# ivo_A_v1_1.net
KiCad netlist of a schematic drawn in EAGLE
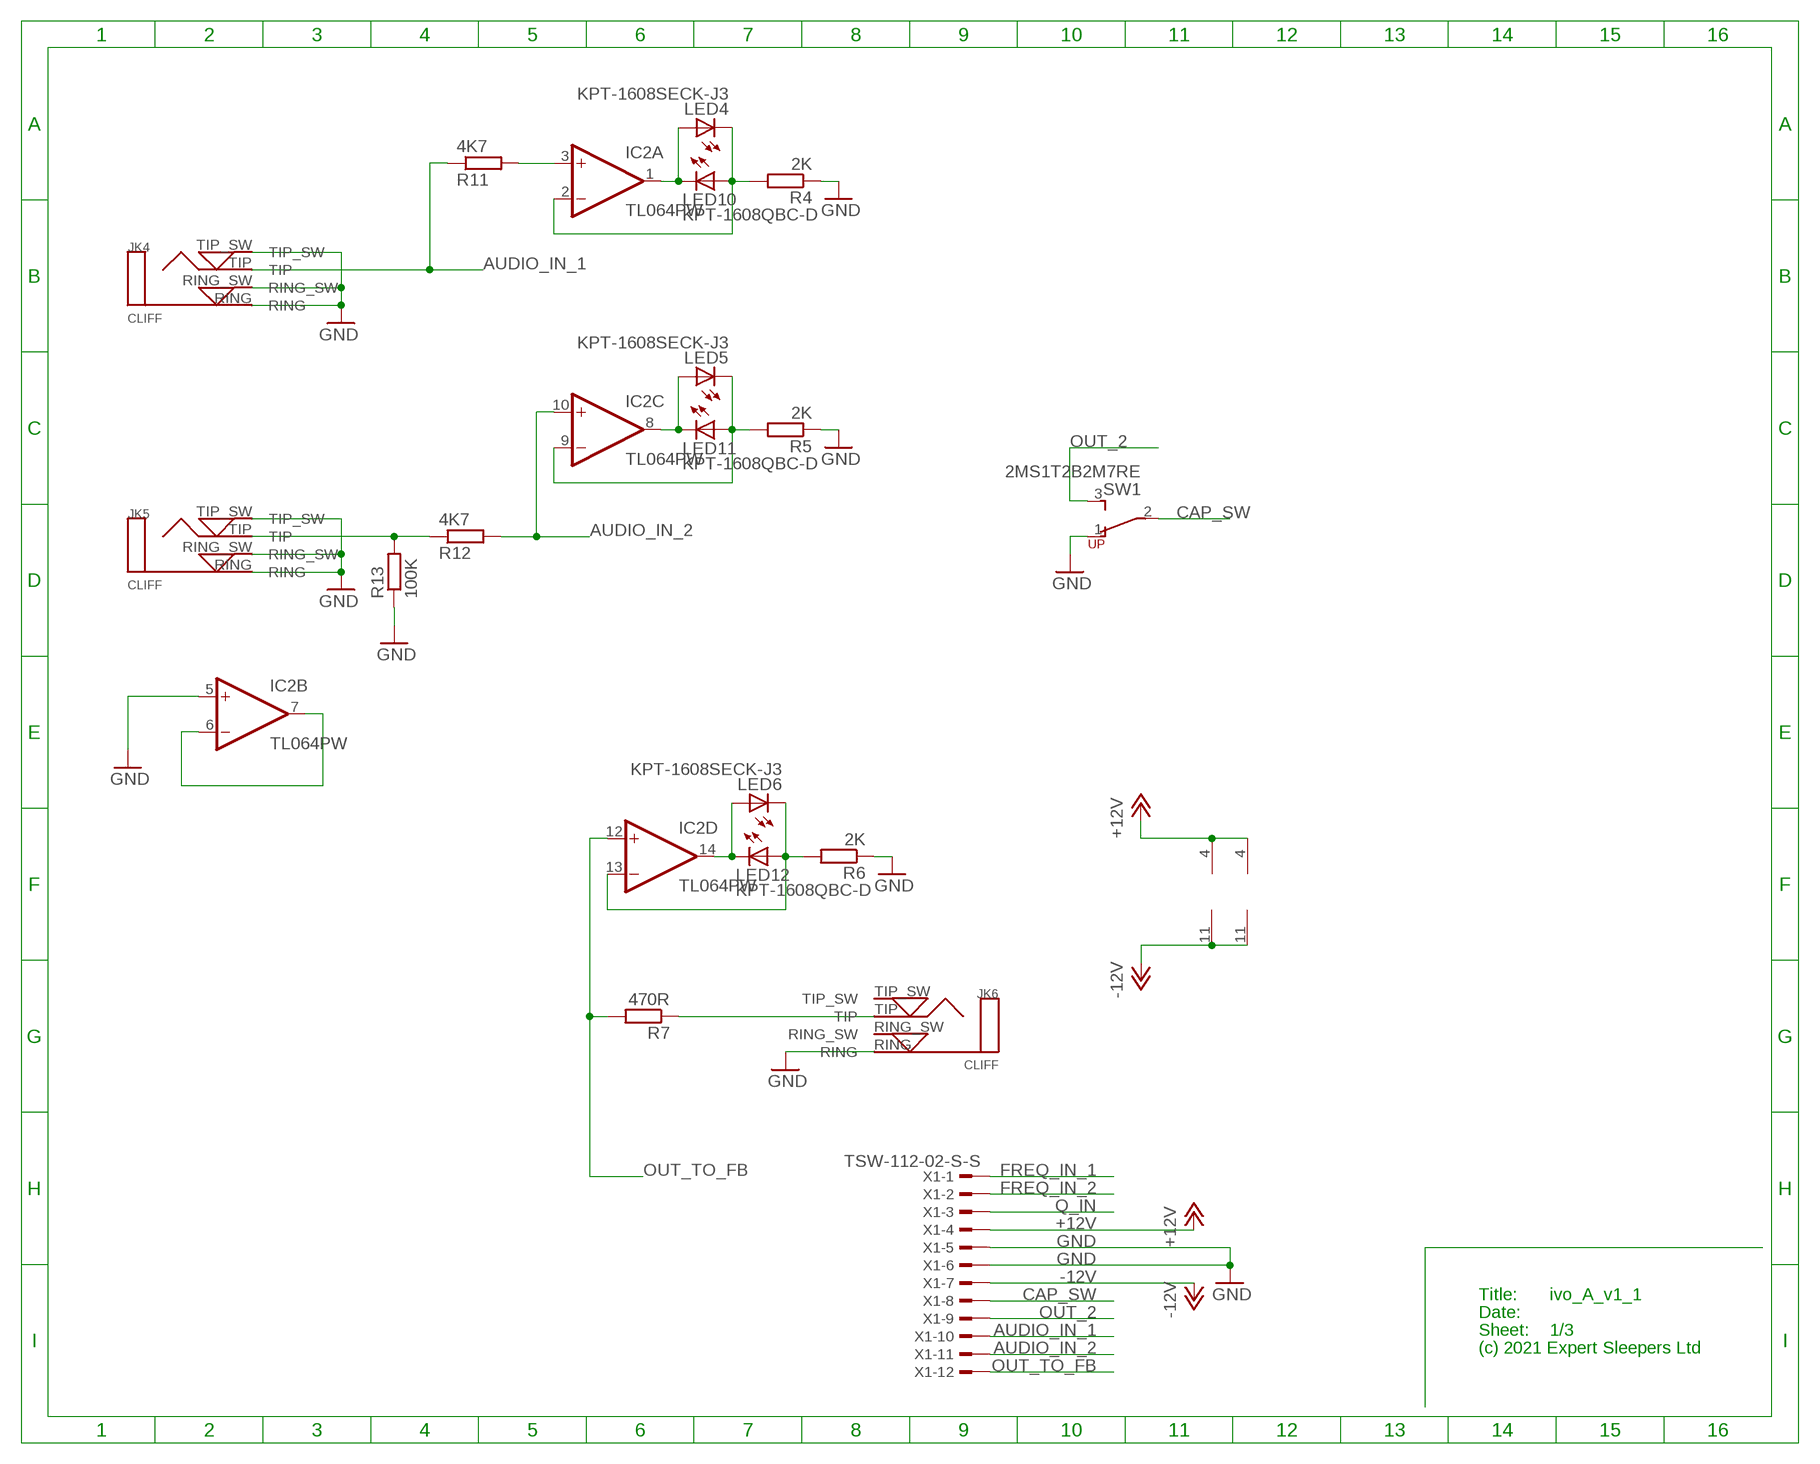
[diagram p0: schematic, sheet 1]
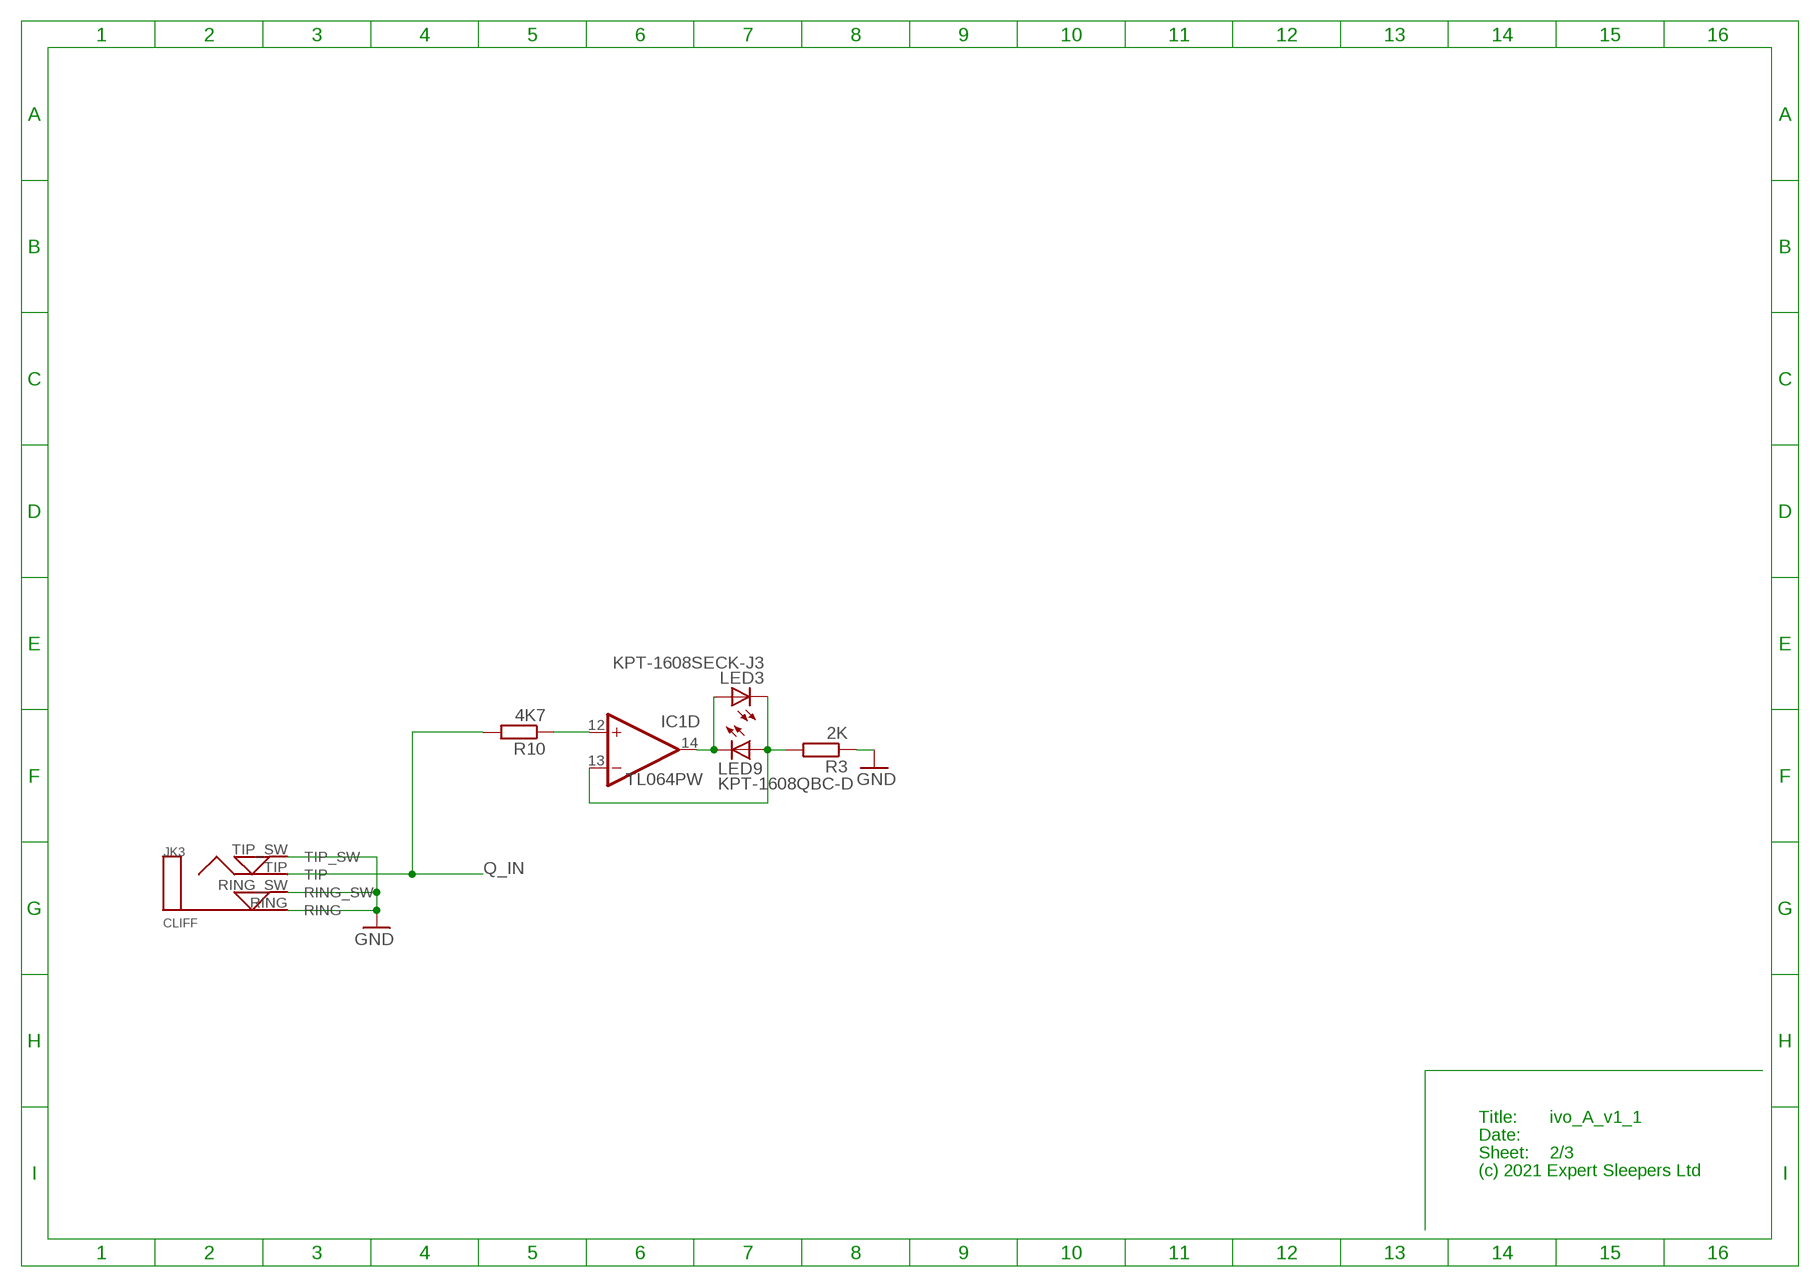
[diagram p1: schematic, sheet 2]
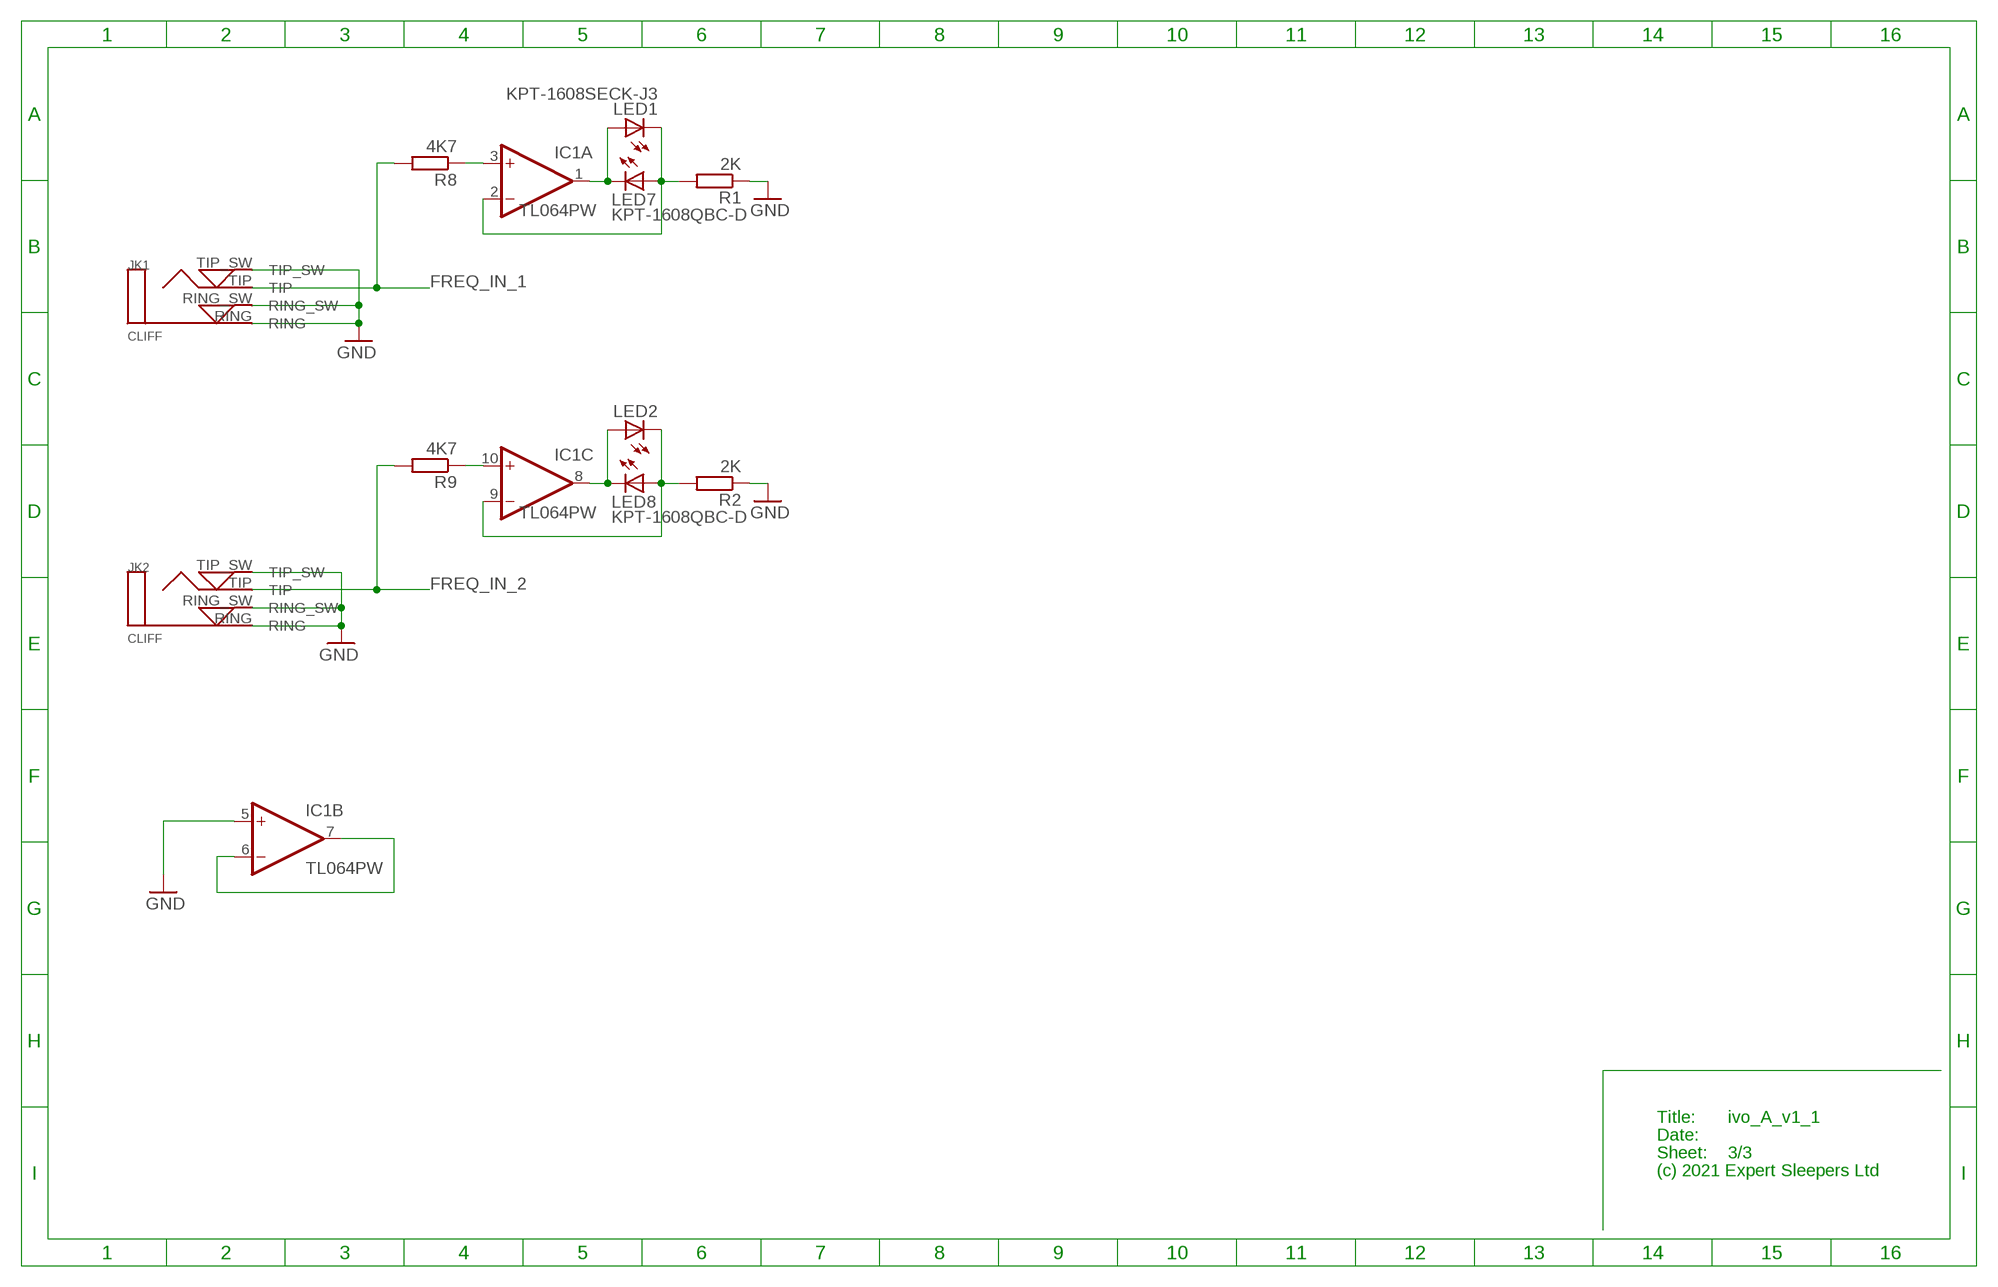
[diagram p2: schematic, sheet 3]

(export (version "E")
  (design (tool "Eeschema 10.0.6"))
  (components
    (comp (ref "IC1")
      (value "TL064PW")
      (footprint "eagle-import:PW_R-PDSO-G14")
      (libsource (lib "eagle-import") (part "TL074PW"))
    )
    (comp (ref "IC2")
      (value "TL064PW")
      (footprint "eagle-import:PW_R-PDSO-G14")
      (libsource (lib "eagle-import") (part "TL074PW"))
    )
    (comp (ref "JK4")
      (value "CLIFF")
      (footprint "eagle-import:CLIFF3.5MMPCB")
      (libsource (lib "eagle-import") (part "CLIFF3.5MM_PCB_SW_JK"))
    )
    (comp (ref "JK5")
      (value "CLIFF")
      (footprint "eagle-import:CLIFF3.5MMPCB")
      (libsource (lib "eagle-import") (part "CLIFF3.5MM_PCB_SW_JK"))
    )
    (comp (ref "JK6")
      (value "CLIFF")
      (footprint "eagle-import:CLIFF3.5MMPCB")
      (libsource (lib "eagle-import") (part "CLIFF3.5MM_PCB_SW_JK"))
    )
    (comp (ref "LED4")
      (value "KPT-1608SECK-J3")
      (footprint "eagle-import:CHIPLED_0603_LEFT")
      (libsource (lib "eagle-import") (part "KPT-1608SECK-J3"))
    )
    (comp (ref "LED5")
      (value "KPT-1608SECK-J3")
      (footprint "eagle-import:CHIPLED_0603_LEFT")
      (libsource (lib "eagle-import") (part "KPT-1608SECK-J3"))
    )
    (comp (ref "LED6")
      (value "KPT-1608SECK-J3")
      (footprint "eagle-import:CHIPLED_0603_LEFT")
      (libsource (lib "eagle-import") (part "KPT-1608SECK-J3"))
    )
    (comp (ref "LED10")
      (value "KPT-1608QBC-D")
      (footprint "eagle-import:CHIPLED_0603_RIGHT")
      (libsource (lib "eagle-import") (part "KPT-1608QBC-D"))
    )
    (comp (ref "LED11")
      (value "KPT-1608QBC-D")
      (footprint "eagle-import:CHIPLED_0603_RIGHT")
      (libsource (lib "eagle-import") (part "KPT-1608QBC-D"))
    )
    (comp (ref "LED12")
      (value "KPT-1608QBC-D")
      (footprint "eagle-import:CHIPLED_0603_RIGHT")
      (libsource (lib "eagle-import") (part "KPT-1608QBC-D"))
    )
    (comp (ref "R4")
      (value "2K")
      (footprint "eagle-import:R1206")
      (libsource (lib "eagle-import") (part "R-EU_R1206"))
    )
    (comp (ref "R5")
      (value "2K")
      (footprint "eagle-import:R1206")
      (libsource (lib "eagle-import") (part "R-EU_R1206"))
    )
    (comp (ref "R6")
      (value "2K")
      (footprint "eagle-import:R1206")
      (libsource (lib "eagle-import") (part "R-EU_R1206"))
    )
    (comp (ref "R7")
      (value "470R")
      (footprint "eagle-import:R1206")
      (libsource (lib "eagle-import") (part "R-EU_R1206"))
    )
    (comp (ref "R11")
      (value "4K7")
      (footprint "eagle-import:R1206")
      (libsource (lib "eagle-import") (part "R-EU_R1206"))
    )
    (comp (ref "R12")
      (value "4K7")
      (footprint "eagle-import:R1206")
      (libsource (lib "eagle-import") (part "R-EU_R1206"))
    )
    (comp (ref "R13")
      (value "100K")
      (footprint "eagle-import:R0603")
      (libsource (lib "eagle-import") (part "R-EU_R0603"))
    )
    (comp (ref "SW1")
      (value "2MS1T2B2M7RE")
      (footprint "eagle-import:2MS1T2B2M7RE")
      (libsource (lib "eagle-import") (part "2MS1T2B2M7RE"))
    )
    (comp (ref "X1")
      (value "TSW-112-02-S-S")
      (footprint "eagle-import:TSW-112-02-S-S")
      (libsource (lib "eagle-import") (part "TSW-112-02-S-S"))
    )
    (comp (ref "JK3")
      (value "CLIFF")
      (footprint "eagle-import:CLIFF3.5MMPCB")
      (libsource (lib "eagle-import") (part "CLIFF3.5MM_PCB_SW_JK"))
    )
    (comp (ref "LED3")
      (value "KPT-1608SECK-J3")
      (footprint "eagle-import:CHIPLED_0603_LEFT")
      (libsource (lib "eagle-import") (part "KPT-1608SECK-J3"))
    )
    (comp (ref "LED9")
      (value "KPT-1608QBC-D")
      (footprint "eagle-import:CHIPLED_0603_RIGHT")
      (libsource (lib "eagle-import") (part "KPT-1608QBC-D"))
    )
    (comp (ref "R3")
      (value "2K")
      (footprint "eagle-import:R1206")
      (libsource (lib "eagle-import") (part "R-EU_R1206"))
    )
    (comp (ref "R10")
      (value "4K7")
      (footprint "eagle-import:R1206")
      (libsource (lib "eagle-import") (part "R-EU_R1206"))
    )
    (comp (ref "JK1")
      (value "CLIFF")
      (footprint "eagle-import:CLIFF3.5MMPCB")
      (libsource (lib "eagle-import") (part "CLIFF3.5MM_PCB_SW_JK"))
    )
    (comp (ref "JK2")
      (value "CLIFF")
      (footprint "eagle-import:CLIFF3.5MMPCB")
      (libsource (lib "eagle-import") (part "CLIFF3.5MM_PCB_SW_JK"))
    )
    (comp (ref "LED1")
      (value "KPT-1608SECK-J3")
      (footprint "eagle-import:CHIPLED_0603_LEFT")
      (libsource (lib "eagle-import") (part "KPT-1608SECK-J3"))
    )
    (comp (ref "LED2")
      (value "KPT-1608SECK-J3")
      (footprint "eagle-import:CHIPLED_0603_LEFT")
      (libsource (lib "eagle-import") (part "KPT-1608SECK-J3"))
    )
    (comp (ref "LED7")
      (value "KPT-1608QBC-D")
      (footprint "eagle-import:CHIPLED_0603_RIGHT")
      (libsource (lib "eagle-import") (part "KPT-1608QBC-D"))
    )
    (comp (ref "LED8")
      (value "KPT-1608QBC-D")
      (footprint "eagle-import:CHIPLED_0603_RIGHT")
      (libsource (lib "eagle-import") (part "KPT-1608QBC-D"))
    )
    (comp (ref "R1")
      (value "2K")
      (footprint "eagle-import:R1206")
      (libsource (lib "eagle-import") (part "R-EU_R1206"))
    )
    (comp (ref "R2")
      (value "2K")
      (footprint "eagle-import:R1206")
      (libsource (lib "eagle-import") (part "R-EU_R1206"))
    )
    (comp (ref "R8")
      (value "4K7")
      (footprint "eagle-import:R1206")
      (libsource (lib "eagle-import") (part "R-EU_R1206"))
    )
    (comp (ref "R9")
      (value "4K7")
      (footprint "eagle-import:R1206")
      (libsource (lib "eagle-import") (part "R-EU_R1206"))
    )
  )
  (nets
    (net (code "1") (name "+12V") (class "Default")
      (node (ref "IC1") (pin "4") (pinfunction "V+_4") (pintype "power_in"))
      (node (ref "IC2") (pin "4") (pinfunction "V+_4") (pintype "power_in"))
      (node (ref "X1") (pin "4") (pinfunction "1_4") (pintype "passive"))
    )
    (net (code "2") (name "-12V") (class "Default")
      (node (ref "IC1") (pin "11") (pinfunction "V-_11") (pintype "power_in"))
      (node (ref "IC2") (pin "11") (pinfunction "V-_11") (pintype "power_in"))
      (node (ref "X1") (pin "7") (pinfunction "1_7") (pintype "passive"))
    )
    (net (code "3") (name "AUDIO_IN_1") (class "Default")
      (node (ref "JK4") (pin "TIP") (pinfunction "TIP_TIP") (pintype "bidirectional"))
      (node (ref "R11") (pin "1") (pinfunction "1_1") (pintype "passive"))
      (node (ref "X1") (pin "10") (pinfunction "1_10") (pintype "passive"))
    )
    (net (code "4") (name "AUDIO_IN_2") (class "Default")
      (node (ref "IC2") (pin "10") (pinfunction "+IN_10") (pintype "input"))
      (node (ref "R12") (pin "2") (pinfunction "2_2") (pintype "passive"))
      (node (ref "X1") (pin "11") (pinfunction "1_11") (pintype "passive"))
    )
    (net (code "5") (name "CAP_SW") (class "Default")
      (node (ref "SW1") (pin "2") (pinfunction "PR_2") (pintype "passive"))
      (node (ref "X1") (pin "8") (pinfunction "1_8") (pintype "passive"))
    )
    (net (code "6") (name "FREQ_IN_1") (class "Default")
      (node (ref "JK1") (pin "TIP") (pinfunction "TIP_TIP") (pintype "bidirectional"))
      (node (ref "R8") (pin "2") (pinfunction "2_2") (pintype "passive"))
      (node (ref "X1") (pin "1") (pinfunction "1_1") (pintype "passive"))
    )
    (net (code "7") (name "FREQ_IN_2") (class "Default")
      (node (ref "JK2") (pin "TIP") (pinfunction "TIP_TIP") (pintype "bidirectional"))
      (node (ref "R9") (pin "2") (pinfunction "2_2") (pintype "passive"))
      (node (ref "X1") (pin "2") (pinfunction "1_2") (pintype "passive"))
    )
    (net (code "8") (name "GND") (class "Default")
      (node (ref "IC1") (pin "5") (pinfunction "+IN_5") (pintype "input"))
      (node (ref "IC2") (pin "5") (pinfunction "+IN_5") (pintype "input"))
      (node (ref "JK1") (pin "RING") (pinfunction "RING_RING") (pintype "bidirectional"))
      (node (ref "JK1") (pin "RING_SW") (pinfunction "RING_SW_RING_SW") (pintype "bidirectional"))
      (node (ref "JK1") (pin "TIP_SW") (pinfunction "TIP_SW_TIP_SW") (pintype "bidirectional"))
      (node (ref "JK2") (pin "RING") (pinfunction "RING_RING") (pintype "bidirectional"))
      (node (ref "JK2") (pin "RING_SW") (pinfunction "RING_SW_RING_SW") (pintype "bidirectional"))
      (node (ref "JK2") (pin "TIP_SW") (pinfunction "TIP_SW_TIP_SW") (pintype "bidirectional"))
      (node (ref "JK3") (pin "RING") (pinfunction "RING_RING") (pintype "bidirectional"))
      (node (ref "JK3") (pin "RING_SW") (pinfunction "RING_SW_RING_SW") (pintype "bidirectional"))
      (node (ref "JK3") (pin "TIP_SW") (pinfunction "TIP_SW_TIP_SW") (pintype "bidirectional"))
      (node (ref "JK4") (pin "RING") (pinfunction "RING_RING") (pintype "bidirectional"))
      (node (ref "JK4") (pin "RING_SW") (pinfunction "RING_SW_RING_SW") (pintype "bidirectional"))
      (node (ref "JK4") (pin "TIP_SW") (pinfunction "TIP_SW_TIP_SW") (pintype "bidirectional"))
      (node (ref "JK5") (pin "RING") (pinfunction "RING_RING") (pintype "bidirectional"))
      (node (ref "JK5") (pin "RING_SW") (pinfunction "RING_SW_RING_SW") (pintype "bidirectional"))
      (node (ref "JK5") (pin "TIP_SW") (pinfunction "TIP_SW_TIP_SW") (pintype "bidirectional"))
      (node (ref "JK6") (pin "RING") (pinfunction "RING_RING") (pintype "bidirectional"))
      (node (ref "R1") (pin "1") (pinfunction "1_1") (pintype "passive"))
      (node (ref "R13") (pin "1") (pinfunction "1_1") (pintype "passive"))
      (node (ref "R2") (pin "1") (pinfunction "1_1") (pintype "passive"))
      (node (ref "R3") (pin "1") (pinfunction "1_1") (pintype "passive"))
      (node (ref "R4") (pin "1") (pinfunction "1_1") (pintype "passive"))
      (node (ref "R5") (pin "1") (pinfunction "1_1") (pintype "passive"))
      (node (ref "R6") (pin "1") (pinfunction "1_1") (pintype "passive"))
      (node (ref "SW1") (pin "1") (pinfunction "RU_1") (pintype "passive"))
      (node (ref "X1") (pin "5") (pinfunction "1_5") (pintype "passive"))
      (node (ref "X1") (pin "6") (pinfunction "1_6") (pintype "passive"))
    )
    (net (code "9") (name "Net-(IC1A-+IN)") (class "Default")
      (node (ref "IC1") (pin "3") (pinfunction "+IN_3") (pintype "input"))
      (node (ref "R8") (pin "1") (pinfunction "1_1") (pintype "passive"))
    )
    (net (code "10") (name "Net-(IC1A--IN)") (class "Default")
      (node (ref "IC1") (pin "2") (pinfunction "-IN_2") (pintype "input"))
      (node (ref "LED1") (pin "1") (pinfunction "C_1") (pintype "passive"))
      (node (ref "LED7") (pin "1") (pinfunction "A_1") (pintype "passive"))
      (node (ref "R1") (pin "2") (pinfunction "2_2") (pintype "passive"))
    )
    (net (code "11") (name "Net-(IC1A-OUT)") (class "Default")
      (node (ref "IC1") (pin "1") (pinfunction "OUT_1") (pintype "output"))
      (node (ref "LED1") (pin "2") (pinfunction "A_2") (pintype "passive"))
      (node (ref "LED7") (pin "2") (pinfunction "C_2") (pintype "passive"))
    )
    (net (code "12") (name "Net-(IC1B--IN)") (class "Default")
      (node (ref "IC1") (pin "6") (pinfunction "-IN_6") (pintype "input"))
      (node (ref "IC1") (pin "7") (pinfunction "OUT_7") (pintype "output"))
    )
    (net (code "13") (name "Net-(IC1C-+IN)") (class "Default")
      (node (ref "IC1") (pin "10") (pinfunction "+IN_10") (pintype "input"))
      (node (ref "R9") (pin "1") (pinfunction "1_1") (pintype "passive"))
    )
    (net (code "14") (name "Net-(IC1C--IN)") (class "Default")
      (node (ref "IC1") (pin "9") (pinfunction "-IN_9") (pintype "input"))
      (node (ref "LED2") (pin "1") (pinfunction "C_1") (pintype "passive"))
      (node (ref "LED8") (pin "1") (pinfunction "A_1") (pintype "passive"))
      (node (ref "R2") (pin "2") (pinfunction "2_2") (pintype "passive"))
    )
    (net (code "15") (name "Net-(IC1C-OUT)") (class "Default")
      (node (ref "IC1") (pin "8") (pinfunction "OUT_8") (pintype "output"))
      (node (ref "LED2") (pin "2") (pinfunction "A_2") (pintype "passive"))
      (node (ref "LED8") (pin "2") (pinfunction "C_2") (pintype "passive"))
    )
    (net (code "16") (name "Net-(IC1D-+IN)") (class "Default")
      (node (ref "IC1") (pin "12") (pinfunction "+IN_12") (pintype "input"))
      (node (ref "R10") (pin "1") (pinfunction "1_1") (pintype "passive"))
    )
    (net (code "17") (name "Net-(IC1D--IN)") (class "Default")
      (node (ref "IC1") (pin "13") (pinfunction "-IN_13") (pintype "input"))
      (node (ref "LED3") (pin "1") (pinfunction "C_1") (pintype "passive"))
      (node (ref "LED9") (pin "1") (pinfunction "A_1") (pintype "passive"))
      (node (ref "R3") (pin "2") (pinfunction "2_2") (pintype "passive"))
    )
    (net (code "18") (name "Net-(IC1D-OUT)") (class "Default")
      (node (ref "IC1") (pin "14") (pinfunction "OUT_14") (pintype "output"))
      (node (ref "LED3") (pin "2") (pinfunction "A_2") (pintype "passive"))
      (node (ref "LED9") (pin "2") (pinfunction "C_2") (pintype "passive"))
    )
    (net (code "19") (name "Net-(IC2A-+IN)") (class "Default")
      (node (ref "IC2") (pin "3") (pinfunction "+IN_3") (pintype "input"))
      (node (ref "R11") (pin "2") (pinfunction "2_2") (pintype "passive"))
    )
    (net (code "20") (name "Net-(IC2A--IN)") (class "Default")
      (node (ref "IC2") (pin "2") (pinfunction "-IN_2") (pintype "input"))
      (node (ref "LED10") (pin "1") (pinfunction "A_1") (pintype "passive"))
      (node (ref "LED4") (pin "1") (pinfunction "C_1") (pintype "passive"))
      (node (ref "R4") (pin "2") (pinfunction "2_2") (pintype "passive"))
    )
    (net (code "21") (name "Net-(IC2A-OUT)") (class "Default")
      (node (ref "IC2") (pin "1") (pinfunction "OUT_1") (pintype "output"))
      (node (ref "LED10") (pin "2") (pinfunction "C_2") (pintype "passive"))
      (node (ref "LED4") (pin "2") (pinfunction "A_2") (pintype "passive"))
    )
    (net (code "22") (name "Net-(IC2B--IN)") (class "Default")
      (node (ref "IC2") (pin "6") (pinfunction "-IN_6") (pintype "input"))
      (node (ref "IC2") (pin "7") (pinfunction "OUT_7") (pintype "output"))
    )
    (net (code "23") (name "Net-(IC2C--IN)") (class "Default")
      (node (ref "IC2") (pin "9") (pinfunction "-IN_9") (pintype "input"))
      (node (ref "LED11") (pin "1") (pinfunction "A_1") (pintype "passive"))
      (node (ref "LED5") (pin "1") (pinfunction "C_1") (pintype "passive"))
      (node (ref "R5") (pin "2") (pinfunction "2_2") (pintype "passive"))
    )
    (net (code "24") (name "Net-(IC2C-OUT)") (class "Default")
      (node (ref "IC2") (pin "8") (pinfunction "OUT_8") (pintype "output"))
      (node (ref "LED11") (pin "2") (pinfunction "C_2") (pintype "passive"))
      (node (ref "LED5") (pin "2") (pinfunction "A_2") (pintype "passive"))
    )
    (net (code "25") (name "Net-(IC2D--IN)") (class "Default")
      (node (ref "IC2") (pin "13") (pinfunction "-IN_13") (pintype "input"))
      (node (ref "LED12") (pin "1") (pinfunction "A_1") (pintype "passive"))
      (node (ref "LED6") (pin "1") (pinfunction "C_1") (pintype "passive"))
      (node (ref "R6") (pin "2") (pinfunction "2_2") (pintype "passive"))
    )
    (net (code "26") (name "Net-(IC2D-OUT)") (class "Default")
      (node (ref "IC2") (pin "14") (pinfunction "OUT_14") (pintype "output"))
      (node (ref "LED12") (pin "2") (pinfunction "C_2") (pintype "passive"))
      (node (ref "LED6") (pin "2") (pinfunction "A_2") (pintype "passive"))
    )
    (net (code "27") (name "Net-(JK5-PadTIP)") (class "Default")
      (node (ref "JK5") (pin "TIP") (pinfunction "TIP_TIP") (pintype "bidirectional"))
      (node (ref "R12") (pin "1") (pinfunction "1_1") (pintype "passive"))
      (node (ref "R13") (pin "2") (pinfunction "2_2") (pintype "passive"))
    )
    (net (code "28") (name "Net-(JK6-PadTIP)") (class "Default")
      (node (ref "JK6") (pin "TIP") (pinfunction "TIP_TIP") (pintype "bidirectional"))
      (node (ref "R7") (pin "1") (pinfunction "1_1") (pintype "passive"))
    )
    (net (code "29") (name "OUT_2") (class "Default")
      (node (ref "SW1") (pin "3") (pinfunction "RD_3") (pintype "passive"))
      (node (ref "X1") (pin "9") (pinfunction "1_9") (pintype "passive"))
    )
    (net (code "30") (name "OUT_TO_FB") (class "Default")
      (node (ref "IC2") (pin "12") (pinfunction "+IN_12") (pintype "input"))
      (node (ref "R7") (pin "2") (pinfunction "2_2") (pintype "passive"))
      (node (ref "X1") (pin "12") (pinfunction "1_12") (pintype "passive"))
    )
    (net (code "31") (name "Q_IN") (class "Default")
      (node (ref "JK3") (pin "TIP") (pinfunction "TIP_TIP") (pintype "bidirectional"))
      (node (ref "R10") (pin "2") (pinfunction "2_2") (pintype "passive"))
      (node (ref "X1") (pin "3") (pinfunction "1_3") (pintype "passive"))
    )
    (net (code "32") (name "unconnected-(JK6-PadRING_SW)") (class "Default")
      (node (ref "JK6") (pin "RING_SW") (pinfunction "RING_SW_RING_SW") (pintype "bidirectional"))
    )
    (net (code "33") (name "unconnected-(JK6-PadTIP_SW)") (class "Default")
      (node (ref "JK6") (pin "TIP_SW") (pinfunction "TIP_SW_TIP_SW") (pintype "bidirectional"))
    )
  )
)
